# 4_-_Ethernet_PHY.net
KiCad netlist of a schematic drawn in Altium Designer
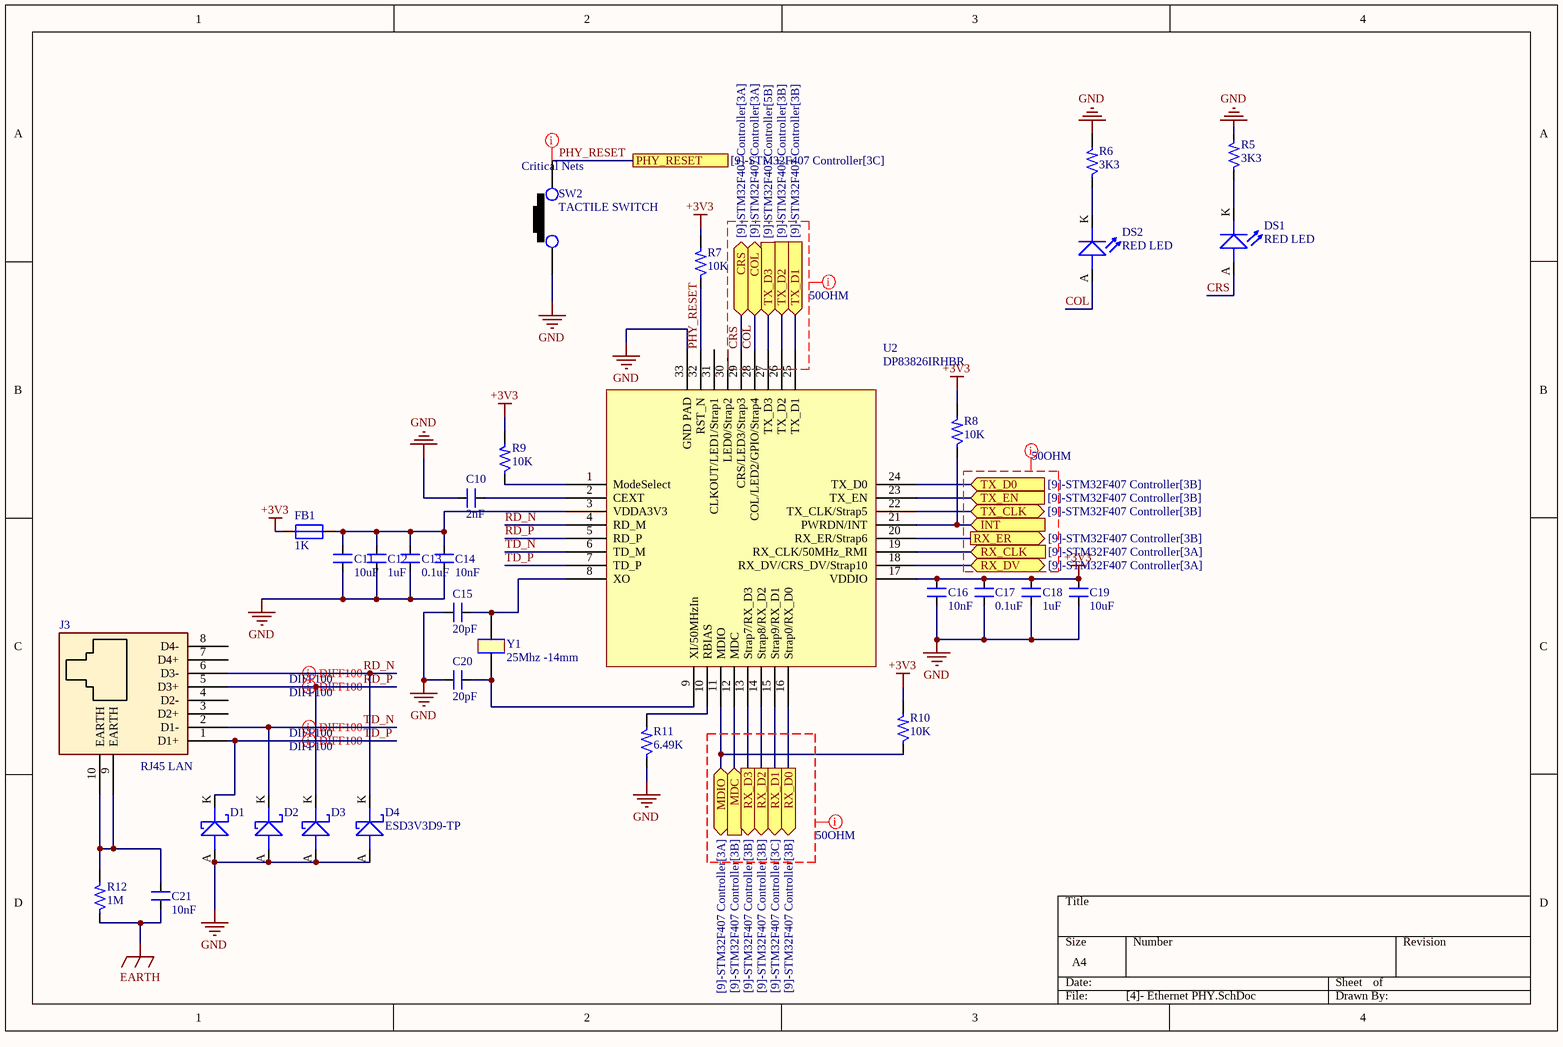
[diagram p0: [4]- Ethernet PHY.SchDoc]

(export (version "E")
  (design (tool "Eeschema 10.0.6"))
  (components
    (comp (ref "C10")
      (value "2nF")
      (footprint "CAP_0805")
      (description "2000pF ±10% 50V Ceramic Capacitor X7R 0805 (2012 Metric)")
      (fields
        (field (name "MANUFACTURER") "Samsung Electro-Mechanics")
        (field (name "MANUFACTURER PART NUMBER") "CL21B202KBANNNC")
      )
      (libsource (lib "ESTEEMPCBLIB") (part "CAP_2nF-50V-10%-0805"))
    )
    (comp (ref "C11")
      (value "10uF")
      (footprint "CAP_1206")
      (description "10µF ±10% 50V Ceramic Capacitor X7R 1206 (3216 Metric)")
      (fields
        (field (name "MANUFACTURER") "KEMET")
        (field (name "MANUFACTURER PART NUMBER") "CL31B106KBHNNNE")
      )
      (libsource (lib "ESTEEMPCBLIB") (part "CAP_10uF-50V-10%-1206"))
    )
    (comp (ref "C12")
      (value "1uF")
      (footprint "CAP_0805")
      (description "1µF ±5% 50V Ceramic Capacitor X7R 0805 (2012 Metric)")
      (fields
        (field (name "MANUFACTURER") "Samsung")
        (field (name "MANUFACTURER PART NUMBER") "CC0805JKX7R9BB105")
      )
      (libsource (lib "ESTEEMPCBLIB") (part "CAP_1uF-50V-5%-0805"))
    )
    (comp (ref "C13")
      (value "0.1uF")
      (footprint "CAP_0805")
      (description "0.1µF ±10% 50V Ceramic Capacitor X7R 0805 (2012 Metric)")
      (fields
        (field (name "MANUFACTURER") "Samsung")
        (field (name "MANUFACTURER PART NUMBER") "CL21B104KBCNNNC")
      )
      (libsource (lib "ESTEEMPCBLIB") (part "CAP_0.1uF-50V-10%-0805"))
    )
    (comp (ref "C14")
      (value "10nF")
      (footprint "CAP_0805")
      (description "10000pF ±10% 50V Ceramic Capacitor X7R 0805 (2012 Metric)")
      (fields
        (field (name "MANUFACTURER") "Samsung")
        (field (name "MANUFACTURER PART NUMBER") "C0805C103K5RECAUTO")
      )
      (libsource (lib "ESTEEMPCBLIB") (part "CAP_10nF-50V-10%-0805"))
    )
    (comp (ref "C15")
      (value "20pF")
      (footprint "CAP_0805")
      (description "±10% 50V Ceramic Capacitor C0G, NP0 0805 (2012 Metric)")
      (fields
        (field (name "MANUFACTURER") "AVX Corporation")
        (field (name "MANUFACTURER PART NUMBER") "08055A200KAT2A")
      )
      (libsource (lib "ESTEEMPCBLIB") (part "CAP_20pF-50V-10%-0805"))
    )
    (comp (ref "C16")
      (value "10nF")
      (footprint "CAP_0805")
      (description "10000pF ±10% 50V Ceramic Capacitor X7R 0805 (2012 Metric)")
      (fields
        (field (name "MANUFACTURER") "Samsung")
        (field (name "MANUFACTURER PART NUMBER") "C0805C103K5RECAUTO")
      )
      (libsource (lib "ESTEEMPCBLIB") (part "CAP_10nF-50V-10%-0805"))
    )
    (comp (ref "C17")
      (value "0.1uF")
      (footprint "CAP_0805")
      (description "0.1µF ±10% 50V Ceramic Capacitor X7R 0805 (2012 Metric)")
      (fields
        (field (name "MANUFACTURER") "Samsung")
        (field (name "MANUFACTURER PART NUMBER") "CL21B104KBCNNNC")
      )
      (libsource (lib "ESTEEMPCBLIB") (part "CAP_0.1uF-50V-10%-0805"))
    )
    (comp (ref "C18")
      (value "1uF")
      (footprint "CAP_0805")
      (description "1µF ±5% 50V Ceramic Capacitor X7R 0805 (2012 Metric)")
      (fields
        (field (name "MANUFACTURER") "Samsung")
        (field (name "MANUFACTURER PART NUMBER") "CC0805JKX7R9BB105")
      )
      (libsource (lib "ESTEEMPCBLIB") (part "CAP_1uF-50V-5%-0805"))
    )
    (comp (ref "C19")
      (value "10uF")
      (footprint "CAP_1206")
      (description "10µF ±10% 50V Ceramic Capacitor X7R 1206 (3216 Metric)")
      (fields
        (field (name "MANUFACTURER") "KEMET")
        (field (name "MANUFACTURER PART NUMBER") "CL31B106KBHNNNE")
      )
      (libsource (lib "ESTEEMPCBLIB") (part "CAP_10uF-50V-10%-1206"))
    )
    (comp (ref "C20")
      (value "20pF")
      (footprint "CAP_0805")
      (description "±10% 50V Ceramic Capacitor C0G, NP0 0805 (2012 Metric)")
      (fields
        (field (name "MANUFACTURER") "AVX Corporation")
        (field (name "MANUFACTURER PART NUMBER") "08055A200KAT2A")
      )
      (libsource (lib "ESTEEMPCBLIB") (part "CAP_20pF-50V-10%-0805"))
    )
    (comp (ref "C21")
      (value "10nF")
      (footprint "CAP_P196_102X287_H332_RAD_TH")
      (description "10000pF ±10% 1000V (1kV) Ceramic Capacitor X7R Radial")
      (fields
        (field (name "MANUFACTURER") "Yageo")
        (field (name "MANUFACTURER PART NUMBER") "RDER73A103K2K1H03B")
      )
      (libsource (lib "ESTEEMPCBLIB") (part "CAP_10nF-1KV-10%-RAD-TH"))
    )
    (comp (ref "D1")
      (value "ESD3V3D9-TP")
      (footprint "DIO_SOD-923")
      (description "8.8V Clamp 5A (8/20µs) Ipp Tvs Diode Surface Mount SOD-923")
      (fields (field (name "MANUFACTURER") "Micro Commercial Co"))
      (libsource (lib "ESTEEMPCBLIB") (part "DIO-T_3.3V-8.8V-SOD923"))
    )
    (comp (ref "D2")
      (value "ESD3V3D9-TP")
      (footprint "DIO_SOD-923")
      (description "8.8V Clamp 5A (8/20µs) Ipp Tvs Diode Surface Mount SOD-923")
      (fields (field (name "MANUFACTURER") "Micro Commercial Co"))
      (libsource (lib "ESTEEMPCBLIB") (part "DIO-T_3.3V-8.8V-SOD923"))
    )
    (comp (ref "D3")
      (value "ESD3V3D9-TP")
      (footprint "DIO_SOD-923")
      (description "8.8V Clamp 5A (8/20µs) Ipp Tvs Diode Surface Mount SOD-923")
      (fields (field (name "MANUFACTURER") "Micro Commercial Co"))
      (libsource (lib "ESTEEMPCBLIB") (part "DIO-T_3.3V-8.8V-SOD923"))
    )
    (comp (ref "D4")
      (value "ESD3V3D9-TP")
      (footprint "DIO_SOD-923")
      (description "8.8V Clamp 5A (8/20µs) Ipp Tvs Diode Surface Mount SOD-923")
      (fields (field (name "MANUFACTURER") "Micro Commercial Co"))
      (libsource (lib "ESTEEMPCBLIB") (part "DIO-T_3.3V-8.8V-SOD923"))
    )
    (comp (ref "DS1")
      (value "RED LED")
      (footprint "LED_0805")
      (description "Red 631nm LED Indication - Discrete 2V 0805 (2012 Metric)")
      (fields
        (field (name "MANUFACTURER") "Vishay Lite-On")
        (field (name "MANUFACTURER PART NUMBER") "LTST-C171KRKT")
      )
      (libsource (lib "ESTEEMPCBLIB") (part "LED_RED-2V-20mA-0805"))
    )
    (comp (ref "DS2")
      (value "RED LED")
      (footprint "LED_0805")
      (description "Red 631nm LED Indication - Discrete 2V 0805 (2012 Metric)")
      (fields
        (field (name "MANUFACTURER") "Vishay Lite-On")
        (field (name "MANUFACTURER PART NUMBER") "LTST-C171KRKT")
      )
      (libsource (lib "ESTEEMPCBLIB") (part "LED_RED-2V-20mA-0805"))
    )
    (comp (ref "FB1")
      (value "1K")
      (footprint "IND_0805")
      (description "1 kOhms @ 100MHz 1 Power Line Ferrite Bead 0805 (2012 Metric) 1.6A")
      (fields
        (field (name "MANUFACTURER") "Laird")
        (field (name "MANUFACTURER PART NUMBER") "BLM21SP102SH1D")
      )
      (libsource (lib "ESTEEMPCBLIB") (part "FB_1K-100MHZ-1.6A-0805"))
    )
    (comp (ref "J3")
      (value "RJ45 LAN")
      (footprint "CON10_P106_RJ45_TH_ST")
      (description "8 Pins, 2 Row 2.54mm Pitch, right angle Connector, male")
      (fields
        (field (name "MANUFACTURER") "Assmann")
        (field (name "MANUFACTURER PART NUMBER") "A-2004-2-4-LPS-N-R")
      )
      (libsource (lib "ESTEEMPCBLIB") (part "CON-SKT-RJ_8C8P-RA-TH"))
    )
    (comp (ref "R5")
      (value "3K3")
      (footprint "RES_0603")
      (description "3.3 kOhms ±1% 0.1W, 1/10W Chip Resistor 0603 (1608 Metric) Automotive AEC-Q200 Thick Film")
      (fields (field (name "MANUFACTURER") "Wilson") (field (name "MANUFACTURER PART NUMBER") "WR06X3301FTL"))
      (libsource (lib "ESTEEMPCBLIB") (part "RES_3.3K-0.1W-1%-0603"))
    )
    (comp (ref "R6")
      (value "3K3")
      (footprint "RES_0603")
      (description "3.3 kOhms ±1% 0.1W, 1/10W Chip Resistor 0603 (1608 Metric) Automotive AEC-Q200 Thick Film")
      (fields (field (name "MANUFACTURER") "Wilson") (field (name "MANUFACTURER PART NUMBER") "WR06X3301FTL"))
      (libsource (lib "ESTEEMPCBLIB") (part "RES_3.3K-0.1W-1%-0603"))
    )
    (comp (ref "R7")
      (value "10K")
      (footprint "RES_0603")
      (description "10 kOhms ±1% 0.1W, 1/10W Chip Resistor 0603 (1608 Metric) Automotive AEC-Q200 Thick Film")
      (fields (field (name "MANUFACTURER") "Walsin") (field (name "MANUFACTURER PART NUMBER") "WR06X1002FTL"))
      (libsource (lib "ESTEEMPCBLIB") (part "RES_10K-0.1W-1%-0603"))
    )
    (comp (ref "R8")
      (value "10K")
      (footprint "RES_0603")
      (description "10 kOhms ±1% 0.1W, 1/10W Chip Resistor 0603 (1608 Metric) Automotive AEC-Q200 Thick Film")
      (fields (field (name "MANUFACTURER") "Walsin") (field (name "MANUFACTURER PART NUMBER") "WR06X1002FTL"))
      (libsource (lib "ESTEEMPCBLIB") (part "RES_10K-0.1W-1%-0603"))
    )
    (comp (ref "R9")
      (value "10K")
      (footprint "RES_0603")
      (description "10 kOhms ±1% 0.1W, 1/10W Chip Resistor 0603 (1608 Metric) Automotive AEC-Q200 Thick Film")
      (fields (field (name "MANUFACTURER") "Walsin") (field (name "MANUFACTURER PART NUMBER") "WR06X1002FTL"))
      (libsource (lib "ESTEEMPCBLIB") (part "RES_10K-0.1W-1%-0603"))
    )
    (comp (ref "R10")
      (value "10K")
      (footprint "RES_0603")
      (description "10 kOhms ±1% 0.1W, 1/10W Chip Resistor 0603 (1608 Metric) Automotive AEC-Q200 Thick Film")
      (fields (field (name "MANUFACTURER") "Walsin") (field (name "MANUFACTURER PART NUMBER") "WR06X1002FTL"))
      (libsource (lib "ESTEEMPCBLIB") (part "RES_10K-0.1W-1%-0603"))
    )
    (comp (ref "R11")
      (value "6.49K")
      (footprint "RES_0805")
      (description "6.49 kOhms ±1% 0.125W, 1/8W Chip Resistor 0805 (2012 Metric) Moisture Resistant Thick Film")
      (fields
        (field (name "MANUFACTURER") "Stackpole Electronics")
        (field (name "MANUFACTURER PART NUMBER") "RC0805FR-076K49L")
      )
      (libsource (lib "ESTEEMPCBLIB") (part "RES_6.49K-0.125W-1%-0805"))
    )
    (comp (ref "R12")
      (value "1M")
      (footprint "RES_1206")
      (fields (field (name "MANUFACTURER") "Walsin") (field (name "MANUFACTURER PART NUMBER") "WR12X1004FTL"))
      (libsource (lib "ESTEEMPCBLIB") (part "RES_1M-0.25W-1%-1206"))
    )
    (comp (ref "SW2")
      (value "TACTILE SWITCH")
      (footprint "SW_342_SMD")
      (description "Tactile Switch SPST-NO Top Actuated Surface Mount")
      (fields
        (field (name "MANUFACTURER") "ITT C&K")
        (field (name "MANUFACTURER PART NUMBER") "RS-282G05A3-SMRT")
      )
      (libsource (lib "ESTEEMPCBLIB") (part "SW1_RS-282G05A3-SMRT-SMD"))
    )
    (comp (ref "U2")
      (value "DP83826IRHBR")
      (footprint "VQFN32_19_218_23X9_SMD")
      (fields (field (name "MANUFACTURER") "Texas Instruments"))
      (libsource (lib "ESTEEMPCBLIB") (part "IC_DP83826IRHBR"))
    )
    (comp (ref "Y1")
      (value "25Mhz -14mm")
      (footprint "XTAL_314_240X47_SMD")
      (description "25MHz ±30ppm Crystal 20pF 30 Ohms HC-49/US")
      (fields
        (field (name "MANUFACTURER") "Abracon")
        (field (name "MANUFACTURER PART NUMBER") "FOXSDLF/250F-20")
      )
      (libsource (lib "ESTEEMPCBLIB") (part "XTAL_25Mhz-FOXSDLF/250F-20"))
    )
  )
  (nets
    (net (code "1") (name "+3V3") (class "Default")
      (node (ref "C16") (pin "2") (pinfunction "2_2") (pintype "passive"))
      (node (ref "C17") (pin "2") (pinfunction "2_2") (pintype "passive"))
      (node (ref "C18") (pin "2") (pinfunction "2_2") (pintype "passive"))
      (node (ref "C19") (pin "2") (pinfunction "2_2") (pintype "passive"))
      (node (ref "FB1") (pin "1") (pinfunction "1_1") (pintype "passive"))
      (node (ref "R10") (pin "2") (pinfunction "2_2") (pintype "passive"))
      (node (ref "R7") (pin "2") (pinfunction "2_2") (pintype "passive"))
      (node (ref "R8") (pin "2") (pinfunction "2_2") (pintype "passive"))
      (node (ref "R9") (pin "2") (pinfunction "2_2") (pintype "passive"))
      (node (ref "U2") (pin "17") (pinfunction "VDDIO_17") (pintype "passive"))
    )
    (net (code "2") (name "/COL") (class "Default")
      (node (ref "DS2") (pin "A") (pinfunction "ANODE_A") (pintype "passive"))
      (node (ref "U2") (pin "28") (pinfunction "COL/LED2/GPIO/Strap4_28") (pintype "passive"))
    )
    (net (code "3") (name "/CRS") (class "Default")
      (node (ref "DS1") (pin "A") (pinfunction "ANODE_A") (pintype "passive"))
      (node (ref "U2") (pin "29") (pinfunction "CRS/LED3/Strap3_29") (pintype "passive"))
    )
    (net (code "4") (name "/INT") (class "Default")
      (node (ref "R8") (pin "1") (pinfunction "1_1") (pintype "passive"))
      (node (ref "U2") (pin "21") (pinfunction "PWRDN/INT_21") (pintype "passive"))
    )
    (net (code "5") (name "/MDC") (class "Default")
      (node (ref "U2") (pin "12") (pinfunction "MDC_12") (pintype "passive"))
    )
    (net (code "6") (name "/MDIO") (class "Default")
      (node (ref "R10") (pin "1") (pinfunction "1_1") (pintype "passive"))
      (node (ref "U2") (pin "11") (pinfunction "MDIO_11") (pintype "passive"))
    )
    (net (code "7") (name "/PHY_RESET") (class "Default")
      (node (ref "R7") (pin "1") (pinfunction "1_1") (pintype "passive"))
      (node (ref "SW2") (pin "2") (pinfunction "2_2") (pintype "passive"))
      (node (ref "U2") (pin "32") (pinfunction "RST_N_32") (pintype "passive"))
    )
    (net (code "8") (name "/RD_N") (class "Default")
      (node (ref "D4") (pin "K") (pinfunction "K_K") (pintype "passive"))
      (node (ref "J3") (pin "6") (pinfunction "D3-_6") (pintype "passive"))
      (node (ref "U2") (pin "4") (pinfunction "RD_M_4") (pintype "passive"))
    )
    (net (code "9") (name "/RD_P") (class "Default")
      (node (ref "D3") (pin "K") (pinfunction "K_K") (pintype "passive"))
      (node (ref "J3") (pin "5") (pinfunction "D3+_5") (pintype "passive"))
      (node (ref "U2") (pin "5") (pinfunction "RD_P_5") (pintype "passive"))
    )
    (net (code "10") (name "/RX_CLK") (class "Default")
      (node (ref "U2") (pin "19") (pinfunction "RX_CLK/50MHz_RMI_19") (pintype "passive"))
    )
    (net (code "11") (name "/RX_D0") (class "Default")
      (node (ref "U2") (pin "16") (pinfunction "Strap0/RX_D0_16") (pintype "passive"))
    )
    (net (code "12") (name "/RX_D1") (class "Default")
      (node (ref "U2") (pin "15") (pinfunction "Strap9/RX_D1_15") (pintype "passive"))
    )
    (net (code "13") (name "/RX_D2") (class "Default")
      (node (ref "U2") (pin "14") (pinfunction "Strap8/RX_D2_14") (pintype "passive"))
    )
    (net (code "14") (name "/RX_D3") (class "Default")
      (node (ref "U2") (pin "13") (pinfunction "Strap7/RX_D3_13") (pintype "passive"))
    )
    (net (code "15") (name "/RX_DV") (class "Default")
      (node (ref "U2") (pin "18") (pinfunction "RX_DV/CRS_DV/Strap10_18") (pintype "passive"))
    )
    (net (code "16") (name "/RX_ER") (class "Default")
      (node (ref "U2") (pin "20") (pinfunction "RX_ER/Strap6_20") (pintype "passive"))
    )
    (net (code "17") (name "/TD_N") (class "Default")
      (node (ref "D2") (pin "K") (pinfunction "K_K") (pintype "passive"))
      (node (ref "J3") (pin "2") (pinfunction "D1-_2") (pintype "passive"))
      (node (ref "U2") (pin "6") (pinfunction "TD_M_6") (pintype "passive"))
    )
    (net (code "18") (name "/TD_P") (class "Default")
      (node (ref "D1") (pin "K") (pinfunction "K_K") (pintype "passive"))
      (node (ref "J3") (pin "1") (pinfunction "D1+_1") (pintype "passive"))
      (node (ref "U2") (pin "7") (pinfunction "TD_P_7") (pintype "passive"))
    )
    (net (code "19") (name "/TX_CLK") (class "Default")
      (node (ref "U2") (pin "22") (pinfunction "TX_CLK/Strap5_22") (pintype "passive"))
    )
    (net (code "20") (name "/TX_D0") (class "Default")
      (node (ref "U2") (pin "24") (pinfunction "TX_D0_24") (pintype "passive"))
    )
    (net (code "21") (name "/TX_D1") (class "Default")
      (node (ref "U2") (pin "25") (pinfunction "TX_D1_25") (pintype "passive"))
    )
    (net (code "22") (name "/TX_D2") (class "Default")
      (node (ref "U2") (pin "26") (pinfunction "TX_D2_26") (pintype "passive"))
    )
    (net (code "23") (name "/TX_D3") (class "Default")
      (node (ref "U2") (pin "27") (pinfunction "TX_D3_27") (pintype "passive"))
    )
    (net (code "24") (name "/TX_EN") (class "Default")
      (node (ref "U2") (pin "23") (pinfunction "TX_EN_23") (pintype "passive"))
    )
    (net (code "25") (name "EARTH") (class "Default")
      (node (ref "C21") (pin "2") (pinfunction "2_2") (pintype "passive"))
      (node (ref "R12") (pin "1") (pinfunction "1_1") (pintype "passive"))
    )
    (net (code "26") (name "GND") (class "Default")
      (node (ref "C10") (pin "1") (pinfunction "1_1") (pintype "passive"))
      (node (ref "C11") (pin "1") (pinfunction "1_1") (pintype "passive"))
      (node (ref "C12") (pin "1") (pinfunction "1_1") (pintype "passive"))
      (node (ref "C13") (pin "1") (pinfunction "1_1") (pintype "passive"))
      (node (ref "C14") (pin "1") (pinfunction "1_1") (pintype "passive"))
      (node (ref "C15") (pin "1") (pinfunction "1_1") (pintype "passive"))
      (node (ref "C16") (pin "1") (pinfunction "1_1") (pintype "passive"))
      (node (ref "C17") (pin "1") (pinfunction "1_1") (pintype "passive"))
      (node (ref "C18") (pin "1") (pinfunction "1_1") (pintype "passive"))
      (node (ref "C19") (pin "1") (pinfunction "1_1") (pintype "passive"))
      (node (ref "C20") (pin "1") (pinfunction "1_1") (pintype "passive"))
      (node (ref "D1") (pin "A") (pinfunction "A_A") (pintype "passive"))
      (node (ref "D2") (pin "A") (pinfunction "A_A") (pintype "passive"))
      (node (ref "D3") (pin "A") (pinfunction "A_A") (pintype "passive"))
      (node (ref "D4") (pin "A") (pinfunction "A_A") (pintype "passive"))
      (node (ref "R11") (pin "1") (pinfunction "1_1") (pintype "passive"))
      (node (ref "R5") (pin "2") (pinfunction "2_2") (pintype "passive"))
      (node (ref "R6") (pin "2") (pinfunction "2_2") (pintype "passive"))
      (node (ref "SW2") (pin "1") (pinfunction "1_1") (pintype "passive"))
      (node (ref "U2") (pin "33") (pinfunction "GND_PAD_33") (pintype "passive"))
    )
    (net (code "27") (name "Net-(C21-Pad1)") (class "Default")
      (node (ref "C21") (pin "1") (pinfunction "1_1") (pintype "passive"))
      (node (ref "J3") (pin "10") (pinfunction "EARTH_10") (pintype "passive"))
      (node (ref "J3") (pin "9") (pinfunction "EARTH_9") (pintype "passive"))
      (node (ref "R12") (pin "2") (pinfunction "2_2") (pintype "passive"))
    )
    (net (code "28") (name "Net-(DS1-CATHODE)") (class "Default")
      (node (ref "DS1") (pin "K") (pinfunction "CATHODE_K") (pintype "passive"))
      (node (ref "R5") (pin "1") (pinfunction "1_1") (pintype "passive"))
    )
    (net (code "29") (name "Net-(DS2-CATHODE)") (class "Default")
      (node (ref "DS2") (pin "K") (pinfunction "CATHODE_K") (pintype "passive"))
      (node (ref "R6") (pin "1") (pinfunction "1_1") (pintype "passive"))
    )
    (net (code "30") (name "Net-(U2-CEXT)") (class "Default")
      (node (ref "C10") (pin "2") (pinfunction "2_2") (pintype "passive"))
      (node (ref "U2") (pin "2") (pinfunction "CEXT_2") (pintype "passive"))
    )
    (net (code "31") (name "Net-(U2-ModeSelect)") (class "Default")
      (node (ref "R9") (pin "1") (pinfunction "1_1") (pintype "passive"))
      (node (ref "U2") (pin "1") (pinfunction "ModeSelect_1") (pintype "passive"))
    )
    (net (code "32") (name "Net-(U2-RBIAS)") (class "Default")
      (node (ref "R11") (pin "2") (pinfunction "2_2") (pintype "passive"))
      (node (ref "U2") (pin "10") (pinfunction "RBIAS_10") (pintype "passive"))
    )
    (net (code "33") (name "Net-(U2-VDDA3V3)") (class "Default")
      (node (ref "C11") (pin "2") (pinfunction "2_2") (pintype "passive"))
      (node (ref "C12") (pin "2") (pinfunction "2_2") (pintype "passive"))
      (node (ref "C13") (pin "2") (pinfunction "2_2") (pintype "passive"))
      (node (ref "C14") (pin "2") (pinfunction "2_2") (pintype "passive"))
      (node (ref "FB1") (pin "2") (pinfunction "2_2") (pintype "passive"))
      (node (ref "U2") (pin "3") (pinfunction "VDDA3V3_3") (pintype "passive"))
    )
    (net (code "34") (name "Net-(U2-XI{slash}50MHzIn)") (class "Default")
      (node (ref "C20") (pin "2") (pinfunction "2_2") (pintype "passive"))
      (node (ref "U2") (pin "9") (pinfunction "XI/50MHzIn_9") (pintype "passive"))
      (node (ref "Y1") (pin "1") (pinfunction "1_1") (pintype "passive"))
    )
    (net (code "35") (name "Net-(U2-XO)") (class "Default")
      (node (ref "C15") (pin "2") (pinfunction "2_2") (pintype "passive"))
      (node (ref "U2") (pin "8") (pinfunction "XO_8") (pintype "passive"))
      (node (ref "Y1") (pin "2") (pinfunction "2_2") (pintype "passive"))
    )
    (net (code "36") (name "unconnected-(J3-D2+-Pad3)") (class "Default")
      (node (ref "J3") (pin "3") (pinfunction "D2+_3") (pintype "passive"))
    )
    (net (code "37") (name "unconnected-(J3-D2--Pad4)") (class "Default")
      (node (ref "J3") (pin "4") (pinfunction "D2-_4") (pintype "passive"))
    )
    (net (code "38") (name "unconnected-(J3-D4+-Pad7)") (class "Default")
      (node (ref "J3") (pin "7") (pinfunction "D4+_7") (pintype "passive"))
    )
    (net (code "39") (name "unconnected-(J3-D4--Pad8)") (class "Default")
      (node (ref "J3") (pin "8") (pinfunction "D4-_8") (pintype "passive"))
    )
    (net (code "40") (name "unconnected-(U2-CLKOUT{slash}LED1{slash}Strap1-Pad31)") (class "Default")
      (node (ref "U2") (pin "31") (pinfunction "CLKOUT/LED1/Strap1_31") (pintype "passive"))
    )
    (net (code "41") (name "unconnected-(U2-LED0{slash}Strap2-Pad30)") (class "Default")
      (node (ref "U2") (pin "30") (pinfunction "LED0/Strap2_30") (pintype "passive"))
    )
  )
)
